# 4_Battery_Heater_Controller.net
KiCad netlist of a schematic drawn in Altium Designer
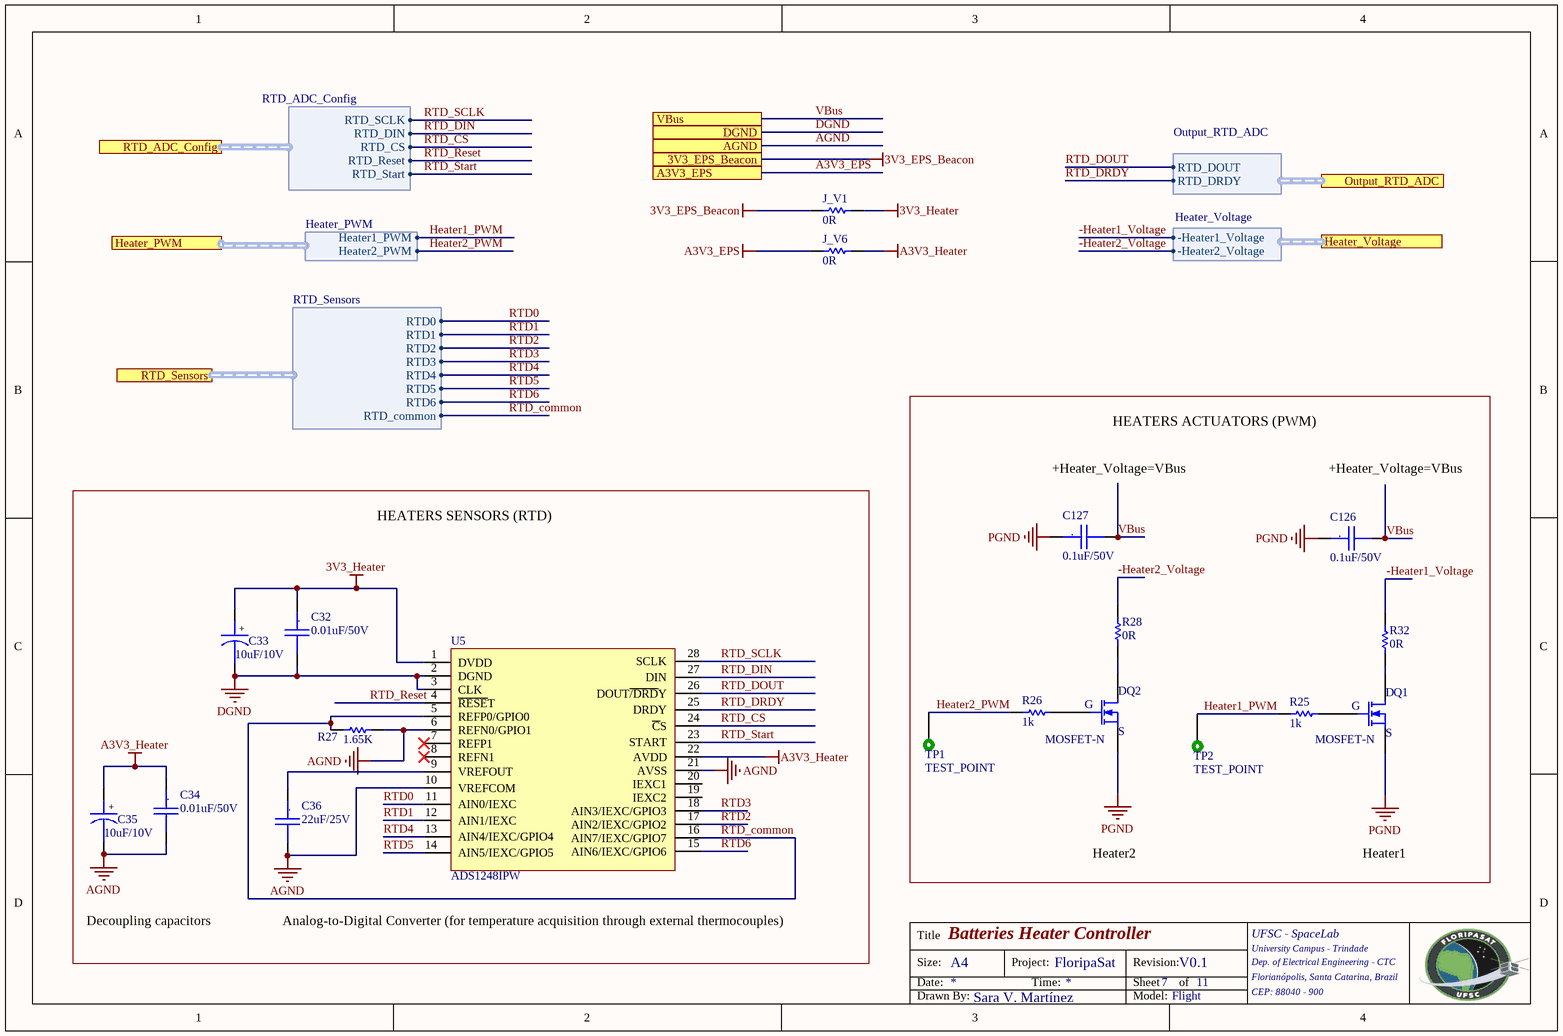
[diagram p0: 4_Battery_Heater_Controller.SchDoc]

(export (version "E")
  (design (tool "Eeschema 10.0.6"))
  (components
    (comp (ref "C32")
      (value "0.01uF/50V")
      (footprint "CC0805")
      (description "CAP CER 0.01uF 50V 10% X7R 0805")
      (fields (field (name "PARTNUMBER") "GRM216R71H103KA01D"))
      (libsource (lib "FloripaSatSchlib") (part "Cap_Cer_X7R_0.01uF_50V_0805"))
    )
    (comp (ref "C33")
      (value "10uF/10V")
      (footprint "FloripaSatPcbLib:CC0805_Tantalum")
      (description "CAP Tantalum 10uF 6.3V 10% 0805")
      (fields (field (name "PARTNUMBER") "TPSR106K006R1000"))
      (libsource (lib "FloripaSatSchlib") (part "Cap_Tant_SMD_10uF_6V3_0805"))
    )
    (comp (ref "C34")
      (value "0.01uF/50V")
      (footprint "CC0805")
      (description "CAP CER 0.01uF 50V 10% X7R 0805")
      (fields (field (name "PARTNUMBER") "GRM216R71H103KA01D"))
      (libsource (lib "FloripaSatSchlib") (part "Cap_Cer_X7R_0.01uF_50V_0805"))
    )
    (comp (ref "C35")
      (value "10uF/10V")
      (footprint "FloripaSatPcbLib:CC0805_Tantalum")
      (description "CAP Tantalum 10uF 6.3V 10% 0805")
      (fields (field (name "PARTNUMBER") "TPSR106K006R1000"))
      (libsource (lib "FloripaSatSchlib") (part "Cap_Tant_SMD_10uF_6V3_0805"))
    )
    (comp (ref "C36")
      (value "22uF/25V")
      (footprint "CC1210")
      (description "CAP CER 22uF 25V 10% X7R 1210")
      (fields (field (name "PARTNUMBER") "GRM31CR71A226KE15L"))
      (libsource (lib "FloripaSatSchlib") (part "Cap_Cer_X7R_0.01uF_16V_1210"))
    )
    (comp (ref "C126")
      (value "0.1uF/50V")
      (footprint "CC0805")
      (description "CAP CER 0.1UF 50V 10% X7R 0805")
      (fields (field (name "PARTNUMBER") "GRM216R71H103KA01D"))
      (libsource (lib "FloripaSatSchlib") (part "Cap_Cer_X7R_0.1uF_25V_0805"))
    )
    (comp (ref "C127")
      (value "0.1uF/50V")
      (footprint "CC0805")
      (description "CAP CER 0.1UF 50V 10% X7R 0805")
      (fields (field (name "PARTNUMBER") "GRM216R71H103KA01D"))
      (libsource (lib "FloripaSatSchlib") (part "Cap_Cer_X7R_0.1uF_25V_0805"))
    )
    (comp (ref "J_V1")
      (value "0R")
      (footprint "FloripaSatPcbLib:0805")
      (description "RES 0R OHM 1/16W JUMPER 0805")
      (fields (field (name "PARTNUMBER") "CRCW08050000Z0EA"))
      (libsource (lib "FloripaSatSchlib") (part "R0R_JUMPER_1/16W_0805"))
    )
    (comp (ref "J_V6")
      (value "0R")
      (footprint "FloripaSatPcbLib:0805")
      (description "RES 0R OHM 1/16W JUMPER 0805")
      (fields (field (name "PARTNUMBER") "CRCW08050000Z0EA"))
      (libsource (lib "FloripaSatSchlib") (part "R0R_JUMPER_1/16W_0805"))
    )
    (comp (ref "Q1")
      (value "MOSFET-N")
      (footprint "SOIC8_Mosfet")
      (description "MOSFET N-Channel 30V")
      (fields (field (name "PARTNUMBER") "SI4010DY-T1-GE3") (field (name "PUBLISHER") "Altium Limited"))
      (libsource (lib "FloripaSatSchlib") (part "MOSFET-N_30V_Si4010DY"))
    )
    (comp (ref "Q2")
      (value "MOSFET-N")
      (footprint "SOIC8_Mosfet")
      (description "MOSFET N-Channel 30V")
      (fields (field (name "PARTNUMBER") "SI4010DY-T1-GE3") (field (name "PUBLISHER") "Altium Limited"))
      (libsource (lib "FloripaSatSchlib") (part "MOSFET-N_30V_Si4010DY"))
    )
    (comp (ref "R25")
      (value "1k")
      (footprint "0805")
      (description "RES 1.0K OHM 1/8W 1% 0805")
      (fields (field (name "PARTNUMBER") "ERJ-6ENF1001V"))
      (libsource (lib "FloripaSatSchlib") (part "R1.0k_1%_1/8W_0805"))
    )
    (comp (ref "R26")
      (value "1k")
      (footprint "0805")
      (description "RES 1.0K OHM 1/8W 1% 0805")
      (fields (field (name "PARTNUMBER") "ERJ-6ENF1001V"))
      (libsource (lib "FloripaSatSchlib") (part "R1.0k_1%_1/8W_0805"))
    )
    (comp (ref "R27")
      (value "1.65K")
      (footprint "0805")
      (description "RES 1.65K OHM 1/10W 0.1% 0805")
      (fields (field (name "PARTNUMBER") "PCF0805R-1K65BT1"))
      (libsource (lib "FloripaSatSchlib") (part "R1.65K_1%_1/10W_0805"))
    )
    (comp (ref "R28")
      (value "0R")
      (footprint "FloripaSatPcbLib:0805")
      (description "RES 0R OHM 1/16W JUMPER 0805")
      (fields (field (name "PARTNUMBER") "CRCW08050000Z0EA"))
      (libsource (lib "FloripaSatSchlib") (part "R0R_JUMPER_1/16W_0805"))
    )
    (comp (ref "R32")
      (value "0R")
      (footprint "FloripaSatPcbLib:0805")
      (description "RES 0R OHM 1/16W JUMPER 0805")
      (fields (field (name "PARTNUMBER") "CRCW08050000Z0EA"))
      (libsource (lib "FloripaSatSchlib") (part "R0R_JUMPER_1/16W_0805"))
    )
    (comp (ref "TP1")
      (value "TEST_POINT")
      (footprint "TEST_POINT")
      (description "Test point")
      (libsource (lib "Floripasat_lib") (part "TEST_POINT"))
    )
    (comp (ref "TP2")
      (value "TEST_POINT")
      (footprint "TEST_POINT")
      (description "Test point")
      (libsource (lib "Floripasat_lib") (part "TEST_POINT"))
    )
    (comp (ref "U5")
      (value "ADS1248IPW")
      (footprint "TSSOP28")
      (description "24 bit ADC Differential Input, SPI, 28-pin TSSOP")
      (fields (field (name "MANUFACTURER") "Texas Instruments") (field (name "PART_NUMBER") "ADS1248IPWR"))
      (libsource (lib "schematic_components") (part "ADS1248IPW"))
    )
  )
  (nets
    (net (code "6") (name "/-Heater1_Voltage") (class "Default")
      (node (ref "R32") (pin "1") (pinfunction "1_1") (pintype "passive"))
    )
    (net (code "7") (name "/-Heater2_Voltage") (class "Default")
      (node (ref "R28") (pin "1") (pinfunction "1_1") (pintype "passive"))
    )
    (net (code "8") (name "/Heater1_PWM") (class "Default")
      (node (ref "R25") (pin "2") (pinfunction "2_2") (pintype "passive"))
      (node (ref "TP2") (pin "1") (pinfunction "1_1") (pintype "passive"))
    )
    (net (code "9") (name "/Heater2_PWM") (class "Default")
      (node (ref "R26") (pin "2") (pinfunction "2_2") (pintype "passive"))
      (node (ref "TP1") (pin "1") (pinfunction "1_1") (pintype "passive"))
    )
    (net (code "10") (name "/RTD0") (class "Default")
      (node (ref "U5") (pin "11") (pinfunction "AIN0/IEXC_11") (pintype "passive"))
    )
    (net (code "11") (name "/RTD1") (class "Default")
      (node (ref "U5") (pin "12") (pinfunction "AIN1/IEXC_12") (pintype "passive"))
    )
    (net (code "12") (name "/RTD2") (class "Default")
      (node (ref "U5") (pin "17") (pinfunction "AIN2/IEXC/GPIO2_17") (pintype "passive"))
    )
    (net (code "13") (name "/RTD3") (class "Default")
      (node (ref "U5") (pin "18") (pinfunction "AIN3/IEXC/GPIO3_18") (pintype "passive"))
    )
    (net (code "14") (name "/RTD4") (class "Default")
      (node (ref "U5") (pin "13") (pinfunction "AIN4/IEXC/GPIO4_13") (pintype "passive"))
    )
    (net (code "15") (name "/RTD5") (class "Default")
      (node (ref "U5") (pin "14") (pinfunction "AIN5/IEXC/GPIO5_14") (pintype "passive"))
    )
    (net (code "16") (name "/RTD6") (class "Default")
      (node (ref "U5") (pin "15") (pinfunction "AIN6/IEXC/GPIO6_15") (pintype "power_in"))
    )
    (net (code "17") (name "/RTD_CS") (class "Default")
      (node (ref "U5") (pin "24") (pinfunction "~{C}S_24") (pintype "passive"))
    )
    (net (code "18") (name "/RTD_DIN") (class "Default")
      (node (ref "U5") (pin "27") (pinfunction "DIN_27") (pintype "passive"))
    )
    (net (code "19") (name "/RTD_DOUT") (class "Default")
      (node (ref "U5") (pin "26") (pinfunction "DOUT~{/DRD}Y_26") (pintype "passive"))
    )
    (net (code "20") (name "/RTD_DRDY") (class "Default")
      (node (ref "U5") (pin "25") (pinfunction "DRDY_25") (pintype "passive"))
    )
    (net (code "21") (name "/RTD_Reset") (class "Default")
      (node (ref "U5") (pin "4") (pinfunction "~{RESE}T_4") (pintype "passive"))
    )
    (net (code "22") (name "/RTD_SCLK") (class "Default")
      (node (ref "U5") (pin "28") (pinfunction "SCLK_28") (pintype "passive"))
    )
    (net (code "23") (name "/RTD_Start") (class "Default")
      (node (ref "U5") (pin "23") (pinfunction "START_23") (pintype "passive"))
    )
    (net (code "24") (name "/RTD_common") (class "Default")
      (node (ref "R27") (pin "2") (pinfunction "2_2") (pintype "passive"))
      (node (ref "U5") (pin "16") (pinfunction "AIN7/IEXC/GPIO7_16") (pintype "power_in"))
      (node (ref "U5") (pin "5") (pinfunction "REFP0/GPIO0_5") (pintype "passive"))
    )
    (net (code "25") (name "/VBus") (class "Default")
      (node (ref "C126") (pin "2") (pinfunction "2_2") (pintype "passive"))
      (node (ref "C127") (pin "2") (pinfunction "2_2") (pintype "passive"))
    )
    (net (code "31") (name "3V3_EPS_Beacon") (class "Default")
      (node (ref "J_V1") (pin "2") (pinfunction "2_2") (pintype "passive"))
    )
    (net (code "32") (name "3V3_Heater") (class "Default")
      (node (ref "C32") (pin "1") (pinfunction "1_1") (pintype "passive"))
      (node (ref "C33") (pin "1") (pinfunction "1_1") (pintype "passive"))
      (node (ref "J_V1") (pin "1") (pinfunction "1_1") (pintype "passive"))
      (node (ref "U5") (pin "1") (pinfunction "DVDD_1") (pintype "power_in"))
    )
    (net (code "33") (name "A3V3_EPS") (class "Default")
      (node (ref "J_V6") (pin "2") (pinfunction "2_2") (pintype "passive"))
    )
    (net (code "34") (name "A3V3_Heater") (class "Default")
      (node (ref "C34") (pin "1") (pinfunction "1_1") (pintype "passive"))
      (node (ref "C35") (pin "1") (pinfunction "1_1") (pintype "passive"))
      (node (ref "J_V6") (pin "1") (pinfunction "1_1") (pintype "passive"))
      (node (ref "U5") (pin "22") (pinfunction "AVDD_22") (pintype "passive"))
    )
    (net (code "35") (name "AGND") (class "Default")
      (node (ref "C34") (pin "2") (pinfunction "2_2") (pintype "passive"))
      (node (ref "C35") (pin "2") (pinfunction "2_2") (pintype "passive"))
      (node (ref "C36") (pin "2") (pinfunction "2_2") (pintype "passive"))
      (node (ref "R27") (pin "1") (pinfunction "1_1") (pintype "passive"))
      (node (ref "U5") (pin "10") (pinfunction "VREFCOM_10") (pintype "passive"))
      (node (ref "U5") (pin "21") (pinfunction "AVSS_21") (pintype "passive"))
      (node (ref "U5") (pin "6") (pinfunction "REFN0/GPIO1_6") (pintype "passive"))
    )
    (net (code "36") (name "DGND") (class "Default")
      (node (ref "C32") (pin "2") (pinfunction "2_2") (pintype "passive"))
      (node (ref "C33") (pin "2") (pinfunction "2_2") (pintype "passive"))
      (node (ref "U5") (pin "2") (pinfunction "DGND_2") (pintype "power_in"))
      (node (ref "U5") (pin "3") (pinfunction "CLK_3") (pintype "passive"))
    )
    (net (code "37") (name "Net-(Q1-D)") (class "Default")
      (node (ref "Q1") (pin "3") (pinfunction "D_3") (pintype "passive"))
      (node (ref "R32") (pin "2") (pinfunction "2_2") (pintype "passive"))
    )
    (net (code "38") (name "Net-(Q1-G)") (class "Default")
      (node (ref "Q1") (pin "2") (pinfunction "G_2") (pintype "passive"))
      (node (ref "R25") (pin "1") (pinfunction "1_1") (pintype "passive"))
    )
    (net (code "39") (name "Net-(Q2-D)") (class "Default")
      (node (ref "Q2") (pin "3") (pinfunction "D_3") (pintype "passive"))
      (node (ref "R28") (pin "2") (pinfunction "2_2") (pintype "passive"))
    )
    (net (code "40") (name "Net-(Q2-G)") (class "Default")
      (node (ref "Q2") (pin "2") (pinfunction "G_2") (pintype "passive"))
      (node (ref "R26") (pin "1") (pinfunction "1_1") (pintype "passive"))
    )
    (net (code "41") (name "Net-(U5-VREFOUT)") (class "Default")
      (node (ref "C36") (pin "1") (pinfunction "1_1") (pintype "passive"))
      (node (ref "U5") (pin "9") (pinfunction "VREFOUT_9") (pintype "passive"))
    )
    (net (code "42") (name "PGND") (class "Default")
      (node (ref "C126") (pin "1") (pinfunction "1_1") (pintype "passive"))
      (node (ref "C127") (pin "1") (pinfunction "1_1") (pintype "passive"))
      (node (ref "Q1") (pin "1") (pinfunction "S_1") (pintype "passive"))
      (node (ref "Q2") (pin "1") (pinfunction "S_1") (pintype "passive"))
    )
    (net (code "43") (name "unconnected-(U5-IEXC1-Pad20)") (class "Default")
      (node (ref "U5") (pin "20") (pinfunction "IEXC1_20") (pintype "passive"))
    )
    (net (code "44") (name "unconnected-(U5-IEXC2-Pad19)") (class "Default")
      (node (ref "U5") (pin "19") (pinfunction "IEXC2_19") (pintype "passive"))
    )
    (net (code "45") (name "unconnected-(U5-REFN1-Pad8)") (class "Default")
      (node (ref "U5") (pin "8") (pinfunction "REFN1_8") (pintype "passive+no_connect"))
    )
    (net (code "46") (name "unconnected-(U5-REFP1-Pad7)") (class "Default")
      (node (ref "U5") (pin "7") (pinfunction "REFP1_7") (pintype "passive+no_connect"))
    )
  )
)
